# connector-bottom-j2-1.net
KiCad netlist of a schematic drawn in Altium Designer
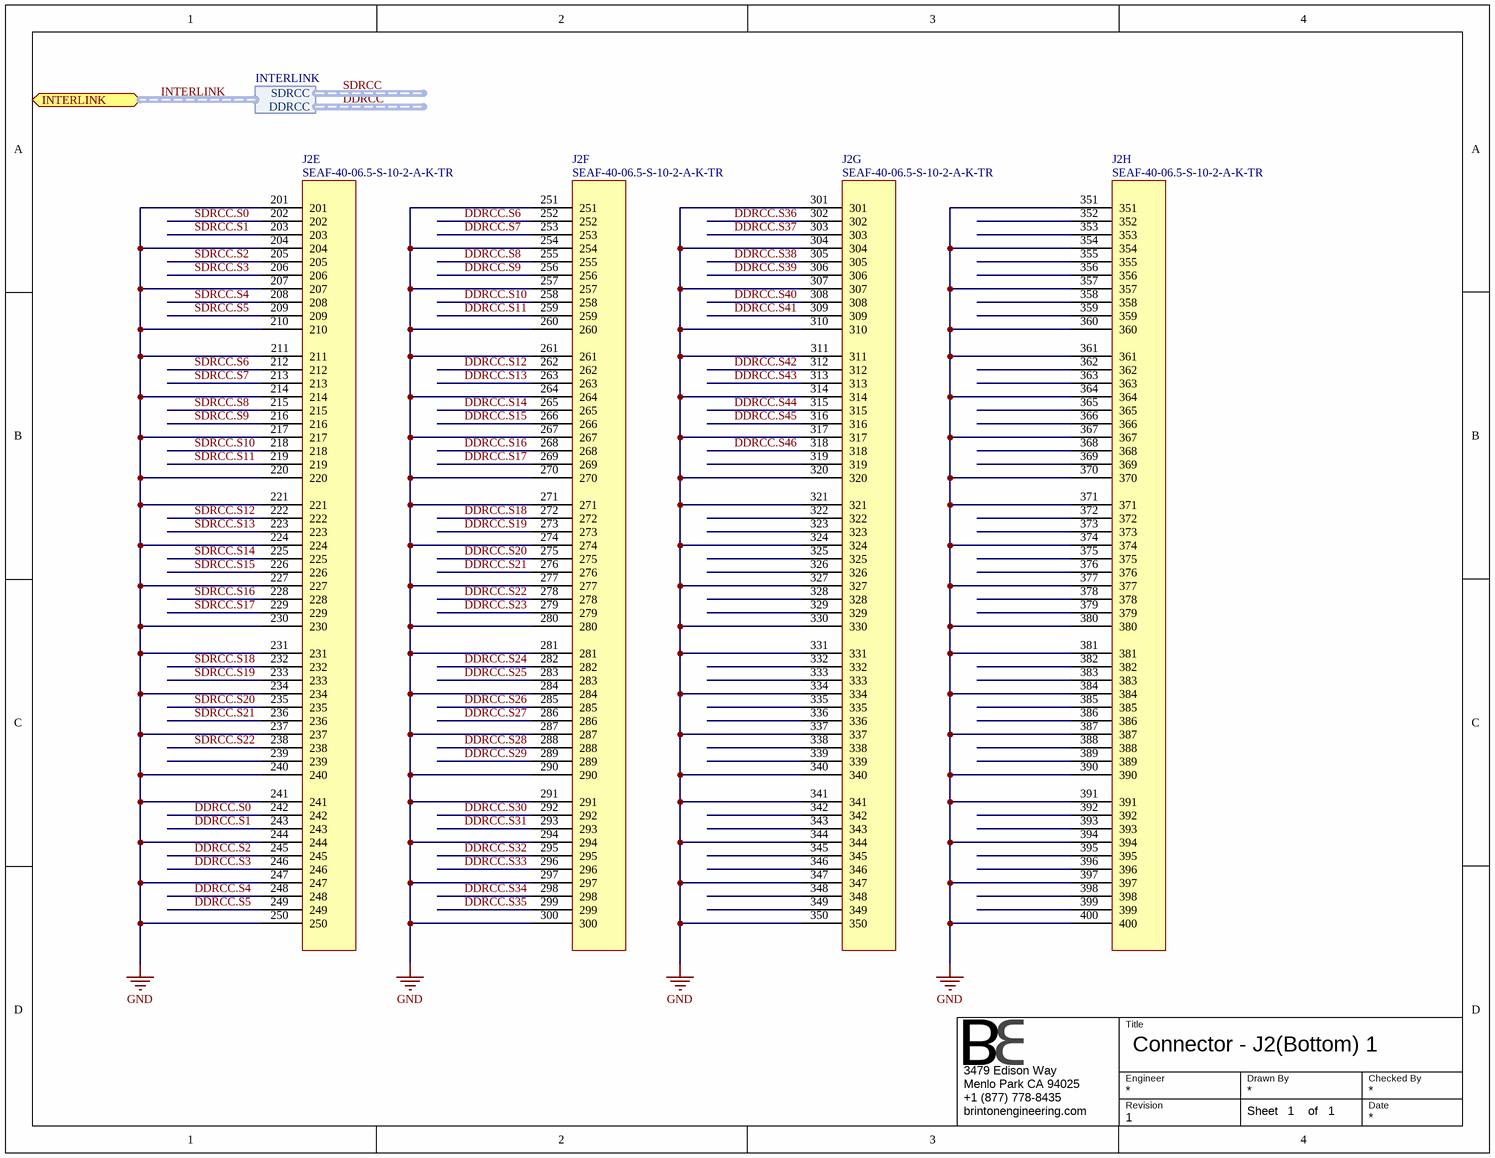
[diagram p0: connector-bottom-j2-1.SchDoc]

(export (version "E")
  (design (tool "Eeschema 10.0.6"))
  (components
    (comp (ref "J2")
      (value "SEAF-40-06.5-S-10-2-A-K-TR")
      (footprint "samtec:SEAF-40-06.5-S-10-2-A-K-TR")
      (description "Terminal Array Assembly, Surface Mount, 0.050\" Pitch, 400 Pins")
      (fields (field (name "MANUFACTURER") "Samtec"))
      (libsource (lib "samtec") (part "SEAF-40-06.5-S-10-2-A-K-TR"))
    )
  )
  (nets
    (net (code "3") (name "/DDRCC.S0") (class "Default")
      (node (ref "J2") (pin "242") (pinfunction "242_242") (pintype "passive"))
    )
    (net (code "4") (name "/DDRCC.S1") (class "Default")
      (node (ref "J2") (pin "243") (pinfunction "243_243") (pintype "passive"))
    )
    (net (code "5") (name "/DDRCC.S2") (class "Default")
      (node (ref "J2") (pin "245") (pinfunction "245_245") (pintype "passive"))
    )
    (net (code "6") (name "/DDRCC.S3") (class "Default")
      (node (ref "J2") (pin "246") (pinfunction "246_246") (pintype "passive"))
    )
    (net (code "7") (name "/DDRCC.S4") (class "Default")
      (node (ref "J2") (pin "248") (pinfunction "248_248") (pintype "passive"))
    )
    (net (code "8") (name "/DDRCC.S5") (class "Default")
      (node (ref "J2") (pin "249") (pinfunction "249_249") (pintype "passive"))
    )
    (net (code "9") (name "/DDRCC.S6") (class "Default")
      (node (ref "J2") (pin "252") (pinfunction "252_252") (pintype "passive"))
    )
    (net (code "10") (name "/DDRCC.S7") (class "Default")
      (node (ref "J2") (pin "253") (pinfunction "253_253") (pintype "passive"))
    )
    (net (code "11") (name "/DDRCC.S8") (class "Default")
      (node (ref "J2") (pin "255") (pinfunction "255_255") (pintype "passive"))
    )
    (net (code "12") (name "/DDRCC.S9") (class "Default")
      (node (ref "J2") (pin "256") (pinfunction "256_256") (pintype "passive"))
    )
    (net (code "13") (name "/DDRCC.S10") (class "Default")
      (node (ref "J2") (pin "258") (pinfunction "258_258") (pintype "passive"))
    )
    (net (code "14") (name "/DDRCC.S11") (class "Default")
      (node (ref "J2") (pin "259") (pinfunction "259_259") (pintype "passive"))
    )
    (net (code "15") (name "/DDRCC.S12") (class "Default")
      (node (ref "J2") (pin "262") (pinfunction "262_262") (pintype "passive"))
    )
    (net (code "16") (name "/DDRCC.S13") (class "Default")
      (node (ref "J2") (pin "263") (pinfunction "263_263") (pintype "passive"))
    )
    (net (code "17") (name "/DDRCC.S14") (class "Default")
      (node (ref "J2") (pin "265") (pinfunction "265_265") (pintype "passive"))
    )
    (net (code "18") (name "/DDRCC.S15") (class "Default")
      (node (ref "J2") (pin "266") (pinfunction "266_266") (pintype "passive"))
    )
    (net (code "19") (name "/DDRCC.S16") (class "Default")
      (node (ref "J2") (pin "268") (pinfunction "268_268") (pintype "passive"))
    )
    (net (code "20") (name "/DDRCC.S17") (class "Default")
      (node (ref "J2") (pin "269") (pinfunction "269_269") (pintype "passive"))
    )
    (net (code "21") (name "/DDRCC.S18") (class "Default")
      (node (ref "J2") (pin "272") (pinfunction "272_272") (pintype "passive"))
    )
    (net (code "22") (name "/DDRCC.S19") (class "Default")
      (node (ref "J2") (pin "273") (pinfunction "273_273") (pintype "passive"))
    )
    (net (code "23") (name "/DDRCC.S20") (class "Default")
      (node (ref "J2") (pin "275") (pinfunction "275_275") (pintype "passive"))
    )
    (net (code "24") (name "/DDRCC.S21") (class "Default")
      (node (ref "J2") (pin "276") (pinfunction "276_276") (pintype "passive"))
    )
    (net (code "25") (name "/DDRCC.S22") (class "Default")
      (node (ref "J2") (pin "278") (pinfunction "278_278") (pintype "passive"))
    )
    (net (code "26") (name "/DDRCC.S23") (class "Default")
      (node (ref "J2") (pin "279") (pinfunction "279_279") (pintype "passive"))
    )
    (net (code "27") (name "/DDRCC.S24") (class "Default")
      (node (ref "J2") (pin "282") (pinfunction "282_282") (pintype "passive"))
    )
    (net (code "28") (name "/DDRCC.S25") (class "Default")
      (node (ref "J2") (pin "283") (pinfunction "283_283") (pintype "passive"))
    )
    (net (code "29") (name "/DDRCC.S26") (class "Default")
      (node (ref "J2") (pin "285") (pinfunction "285_285") (pintype "passive"))
    )
    (net (code "30") (name "/DDRCC.S27") (class "Default")
      (node (ref "J2") (pin "286") (pinfunction "286_286") (pintype "passive"))
    )
    (net (code "31") (name "/DDRCC.S28") (class "Default")
      (node (ref "J2") (pin "288") (pinfunction "288_288") (pintype "passive"))
    )
    (net (code "32") (name "/DDRCC.S29") (class "Default")
      (node (ref "J2") (pin "289") (pinfunction "289_289") (pintype "passive"))
    )
    (net (code "33") (name "/DDRCC.S30") (class "Default")
      (node (ref "J2") (pin "292") (pinfunction "292_292") (pintype "passive"))
    )
    (net (code "34") (name "/DDRCC.S31") (class "Default")
      (node (ref "J2") (pin "293") (pinfunction "293_293") (pintype "passive"))
    )
    (net (code "35") (name "/DDRCC.S32") (class "Default")
      (node (ref "J2") (pin "295") (pinfunction "295_295") (pintype "passive"))
    )
    (net (code "36") (name "/DDRCC.S33") (class "Default")
      (node (ref "J2") (pin "296") (pinfunction "296_296") (pintype "passive"))
    )
    (net (code "37") (name "/DDRCC.S34") (class "Default")
      (node (ref "J2") (pin "298") (pinfunction "298_298") (pintype "passive"))
    )
    (net (code "38") (name "/DDRCC.S35") (class "Default")
      (node (ref "J2") (pin "299") (pinfunction "299_299") (pintype "passive"))
    )
    (net (code "39") (name "/DDRCC.S36") (class "Default")
      (node (ref "J2") (pin "302") (pinfunction "302_302") (pintype "passive"))
    )
    (net (code "40") (name "/DDRCC.S37") (class "Default")
      (node (ref "J2") (pin "303") (pinfunction "303_303") (pintype "passive"))
    )
    (net (code "41") (name "/DDRCC.S38") (class "Default")
      (node (ref "J2") (pin "305") (pinfunction "305_305") (pintype "passive"))
    )
    (net (code "42") (name "/DDRCC.S39") (class "Default")
      (node (ref "J2") (pin "306") (pinfunction "306_306") (pintype "passive"))
    )
    (net (code "43") (name "/DDRCC.S40") (class "Default")
      (node (ref "J2") (pin "308") (pinfunction "308_308") (pintype "passive"))
    )
    (net (code "44") (name "/DDRCC.S41") (class "Default")
      (node (ref "J2") (pin "309") (pinfunction "309_309") (pintype "passive"))
    )
    (net (code "45") (name "/DDRCC.S42") (class "Default")
      (node (ref "J2") (pin "312") (pinfunction "312_312") (pintype "passive"))
    )
    (net (code "46") (name "/DDRCC.S43") (class "Default")
      (node (ref "J2") (pin "313") (pinfunction "313_313") (pintype "passive"))
    )
    (net (code "47") (name "/DDRCC.S44") (class "Default")
      (node (ref "J2") (pin "315") (pinfunction "315_315") (pintype "passive"))
    )
    (net (code "48") (name "/DDRCC.S45") (class "Default")
      (node (ref "J2") (pin "316") (pinfunction "316_316") (pintype "passive"))
    )
    (net (code "49") (name "/DDRCC.S46") (class "Default")
      (node (ref "J2") (pin "318") (pinfunction "318_318") (pintype "passive"))
    )
    (net (code "51") (name "/SDRCC.S0") (class "Default")
      (node (ref "J2") (pin "202") (pinfunction "202_202") (pintype "passive"))
    )
    (net (code "52") (name "/SDRCC.S1") (class "Default")
      (node (ref "J2") (pin "203") (pinfunction "203_203") (pintype "passive"))
    )
    (net (code "53") (name "/SDRCC.S2") (class "Default")
      (node (ref "J2") (pin "205") (pinfunction "205_205") (pintype "passive"))
    )
    (net (code "54") (name "/SDRCC.S3") (class "Default")
      (node (ref "J2") (pin "206") (pinfunction "206_206") (pintype "passive"))
    )
    (net (code "55") (name "/SDRCC.S4") (class "Default")
      (node (ref "J2") (pin "208") (pinfunction "208_208") (pintype "passive"))
    )
    (net (code "56") (name "/SDRCC.S5") (class "Default")
      (node (ref "J2") (pin "209") (pinfunction "209_209") (pintype "passive"))
    )
    (net (code "57") (name "/SDRCC.S6") (class "Default")
      (node (ref "J2") (pin "212") (pinfunction "212_212") (pintype "passive"))
    )
    (net (code "58") (name "/SDRCC.S7") (class "Default")
      (node (ref "J2") (pin "213") (pinfunction "213_213") (pintype "passive"))
    )
    (net (code "59") (name "/SDRCC.S8") (class "Default")
      (node (ref "J2") (pin "215") (pinfunction "215_215") (pintype "passive"))
    )
    (net (code "60") (name "/SDRCC.S9") (class "Default")
      (node (ref "J2") (pin "216") (pinfunction "216_216") (pintype "passive"))
    )
    (net (code "61") (name "/SDRCC.S10") (class "Default")
      (node (ref "J2") (pin "218") (pinfunction "218_218") (pintype "passive"))
    )
    (net (code "62") (name "/SDRCC.S11") (class "Default")
      (node (ref "J2") (pin "219") (pinfunction "219_219") (pintype "passive"))
    )
    (net (code "63") (name "/SDRCC.S12") (class "Default")
      (node (ref "J2") (pin "222") (pinfunction "222_222") (pintype "passive"))
    )
    (net (code "64") (name "/SDRCC.S13") (class "Default")
      (node (ref "J2") (pin "223") (pinfunction "223_223") (pintype "passive"))
    )
    (net (code "65") (name "/SDRCC.S14") (class "Default")
      (node (ref "J2") (pin "225") (pinfunction "225_225") (pintype "passive"))
    )
    (net (code "66") (name "/SDRCC.S15") (class "Default")
      (node (ref "J2") (pin "226") (pinfunction "226_226") (pintype "passive"))
    )
    (net (code "67") (name "/SDRCC.S16") (class "Default")
      (node (ref "J2") (pin "228") (pinfunction "228_228") (pintype "passive"))
    )
    (net (code "68") (name "/SDRCC.S17") (class "Default")
      (node (ref "J2") (pin "229") (pinfunction "229_229") (pintype "passive"))
    )
    (net (code "69") (name "/SDRCC.S18") (class "Default")
      (node (ref "J2") (pin "232") (pinfunction "232_232") (pintype "passive"))
    )
    (net (code "70") (name "/SDRCC.S19") (class "Default")
      (node (ref "J2") (pin "233") (pinfunction "233_233") (pintype "passive"))
    )
    (net (code "71") (name "/SDRCC.S20") (class "Default")
      (node (ref "J2") (pin "235") (pinfunction "235_235") (pintype "passive"))
    )
    (net (code "72") (name "/SDRCC.S21") (class "Default")
      (node (ref "J2") (pin "236") (pinfunction "236_236") (pintype "passive"))
    )
    (net (code "73") (name "/SDRCC.S22") (class "Default")
      (node (ref "J2") (pin "238") (pinfunction "238_238") (pintype "passive"))
    )
    (net (code "75") (name "GND") (class "Default")
      (node (ref "J2") (pin "201") (pinfunction "201_201") (pintype "passive"))
      (node (ref "J2") (pin "204") (pinfunction "204_204") (pintype "passive"))
      (node (ref "J2") (pin "207") (pinfunction "207_207") (pintype "passive"))
      (node (ref "J2") (pin "210") (pinfunction "210_210") (pintype "passive"))
      (node (ref "J2") (pin "211") (pinfunction "211_211") (pintype "passive"))
      (node (ref "J2") (pin "214") (pinfunction "214_214") (pintype "passive"))
      (node (ref "J2") (pin "217") (pinfunction "217_217") (pintype "passive"))
      (node (ref "J2") (pin "220") (pinfunction "220_220") (pintype "passive"))
      (node (ref "J2") (pin "221") (pinfunction "221_221") (pintype "passive"))
      (node (ref "J2") (pin "224") (pinfunction "224_224") (pintype "passive"))
      (node (ref "J2") (pin "227") (pinfunction "227_227") (pintype "passive"))
      (node (ref "J2") (pin "230") (pinfunction "230_230") (pintype "passive"))
      (node (ref "J2") (pin "231") (pinfunction "231_231") (pintype "passive"))
      (node (ref "J2") (pin "234") (pinfunction "234_234") (pintype "passive"))
      (node (ref "J2") (pin "237") (pinfunction "237_237") (pintype "passive"))
      (node (ref "J2") (pin "240") (pinfunction "240_240") (pintype "passive"))
      (node (ref "J2") (pin "241") (pinfunction "241_241") (pintype "passive"))
      (node (ref "J2") (pin "244") (pinfunction "244_244") (pintype "passive"))
      (node (ref "J2") (pin "247") (pinfunction "247_247") (pintype "passive"))
      (node (ref "J2") (pin "250") (pinfunction "250_250") (pintype "passive"))
      (node (ref "J2") (pin "251") (pinfunction "251_251") (pintype "passive"))
      (node (ref "J2") (pin "254") (pinfunction "254_254") (pintype "passive"))
      (node (ref "J2") (pin "257") (pinfunction "257_257") (pintype "passive"))
      (node (ref "J2") (pin "260") (pinfunction "260_260") (pintype "passive"))
      (node (ref "J2") (pin "261") (pinfunction "261_261") (pintype "passive"))
      (node (ref "J2") (pin "264") (pinfunction "264_264") (pintype "passive"))
      (node (ref "J2") (pin "267") (pinfunction "267_267") (pintype "passive"))
      (node (ref "J2") (pin "270") (pinfunction "270_270") (pintype "passive"))
      (node (ref "J2") (pin "271") (pinfunction "271_271") (pintype "passive"))
      (node (ref "J2") (pin "274") (pinfunction "274_274") (pintype "passive"))
      (node (ref "J2") (pin "277") (pinfunction "277_277") (pintype "passive"))
      (node (ref "J2") (pin "280") (pinfunction "280_280") (pintype "passive"))
      (node (ref "J2") (pin "281") (pinfunction "281_281") (pintype "passive"))
      (node (ref "J2") (pin "284") (pinfunction "284_284") (pintype "passive"))
      (node (ref "J2") (pin "287") (pinfunction "287_287") (pintype "passive"))
      (node (ref "J2") (pin "290") (pinfunction "290_290") (pintype "passive"))
      (node (ref "J2") (pin "291") (pinfunction "291_291") (pintype "passive"))
      (node (ref "J2") (pin "294") (pinfunction "294_294") (pintype "passive"))
      (node (ref "J2") (pin "297") (pinfunction "297_297") (pintype "passive"))
      (node (ref "J2") (pin "300") (pinfunction "300_300") (pintype "passive"))
      (node (ref "J2") (pin "301") (pinfunction "301_301") (pintype "passive"))
      (node (ref "J2") (pin "304") (pinfunction "304_304") (pintype "passive"))
      (node (ref "J2") (pin "307") (pinfunction "307_307") (pintype "passive"))
      (node (ref "J2") (pin "310") (pinfunction "310_310") (pintype "passive"))
      (node (ref "J2") (pin "311") (pinfunction "311_311") (pintype "passive"))
      (node (ref "J2") (pin "314") (pinfunction "314_314") (pintype "passive"))
      (node (ref "J2") (pin "317") (pinfunction "317_317") (pintype "passive"))
      (node (ref "J2") (pin "320") (pinfunction "320_320") (pintype "passive"))
      (node (ref "J2") (pin "321") (pinfunction "321_321") (pintype "passive"))
      (node (ref "J2") (pin "324") (pinfunction "324_324") (pintype "passive"))
      (node (ref "J2") (pin "327") (pinfunction "327_327") (pintype "passive"))
      (node (ref "J2") (pin "330") (pinfunction "330_330") (pintype "passive"))
      (node (ref "J2") (pin "331") (pinfunction "331_331") (pintype "passive"))
      (node (ref "J2") (pin "334") (pinfunction "334_334") (pintype "passive"))
      (node (ref "J2") (pin "337") (pinfunction "337_337") (pintype "passive"))
      (node (ref "J2") (pin "340") (pinfunction "340_340") (pintype "passive"))
      (node (ref "J2") (pin "341") (pinfunction "341_341") (pintype "passive"))
      (node (ref "J2") (pin "344") (pinfunction "344_344") (pintype "passive"))
      (node (ref "J2") (pin "347") (pinfunction "347_347") (pintype "passive"))
      (node (ref "J2") (pin "350") (pinfunction "350_350") (pintype "passive"))
      (node (ref "J2") (pin "351") (pinfunction "351_351") (pintype "passive"))
      (node (ref "J2") (pin "354") (pinfunction "354_354") (pintype "passive"))
      (node (ref "J2") (pin "357") (pinfunction "357_357") (pintype "passive"))
      (node (ref "J2") (pin "360") (pinfunction "360_360") (pintype "passive"))
      (node (ref "J2") (pin "361") (pinfunction "361_361") (pintype "passive"))
      (node (ref "J2") (pin "364") (pinfunction "364_364") (pintype "passive"))
      (node (ref "J2") (pin "367") (pinfunction "367_367") (pintype "passive"))
      (node (ref "J2") (pin "370") (pinfunction "370_370") (pintype "passive"))
      (node (ref "J2") (pin "371") (pinfunction "371_371") (pintype "passive"))
      (node (ref "J2") (pin "374") (pinfunction "374_374") (pintype "passive"))
      (node (ref "J2") (pin "377") (pinfunction "377_377") (pintype "passive"))
      (node (ref "J2") (pin "380") (pinfunction "380_380") (pintype "passive"))
      (node (ref "J2") (pin "381") (pinfunction "381_381") (pintype "passive"))
      (node (ref "J2") (pin "384") (pinfunction "384_384") (pintype "passive"))
      (node (ref "J2") (pin "387") (pinfunction "387_387") (pintype "passive"))
      (node (ref "J2") (pin "390") (pinfunction "390_390") (pintype "passive"))
      (node (ref "J2") (pin "391") (pinfunction "391_391") (pintype "passive"))
      (node (ref "J2") (pin "394") (pinfunction "394_394") (pintype "passive"))
      (node (ref "J2") (pin "397") (pinfunction "397_397") (pintype "passive"))
      (node (ref "J2") (pin "400") (pinfunction "400_400") (pintype "passive"))
    )
    (net (code "76") (name "unconnected-(J2-Pad239)") (class "Default")
      (node (ref "J2") (pin "239") (pinfunction "239_239") (pintype "passive"))
    )
    (net (code "77") (name "unconnected-(J2-Pad319)") (class "Default")
      (node (ref "J2") (pin "319") (pinfunction "319_319") (pintype "passive"))
    )
    (net (code "78") (name "unconnected-(J2-Pad322)") (class "Default")
      (node (ref "J2") (pin "322") (pinfunction "322_322") (pintype "passive"))
    )
    (net (code "79") (name "unconnected-(J2-Pad323)") (class "Default")
      (node (ref "J2") (pin "323") (pinfunction "323_323") (pintype "passive"))
    )
    (net (code "80") (name "unconnected-(J2-Pad325)") (class "Default")
      (node (ref "J2") (pin "325") (pinfunction "325_325") (pintype "passive"))
    )
    (net (code "81") (name "unconnected-(J2-Pad326)") (class "Default")
      (node (ref "J2") (pin "326") (pinfunction "326_326") (pintype "passive"))
    )
    (net (code "82") (name "unconnected-(J2-Pad328)") (class "Default")
      (node (ref "J2") (pin "328") (pinfunction "328_328") (pintype "passive"))
    )
    (net (code "83") (name "unconnected-(J2-Pad329)") (class "Default")
      (node (ref "J2") (pin "329") (pinfunction "329_329") (pintype "passive"))
    )
    (net (code "84") (name "unconnected-(J2-Pad332)") (class "Default")
      (node (ref "J2") (pin "332") (pinfunction "332_332") (pintype "passive"))
    )
    (net (code "85") (name "unconnected-(J2-Pad333)") (class "Default")
      (node (ref "J2") (pin "333") (pinfunction "333_333") (pintype "passive"))
    )
    (net (code "86") (name "unconnected-(J2-Pad335)") (class "Default")
      (node (ref "J2") (pin "335") (pinfunction "335_335") (pintype "passive"))
    )
    (net (code "87") (name "unconnected-(J2-Pad336)") (class "Default")
      (node (ref "J2") (pin "336") (pinfunction "336_336") (pintype "passive"))
    )
    (net (code "88") (name "unconnected-(J2-Pad338)") (class "Default")
      (node (ref "J2") (pin "338") (pinfunction "338_338") (pintype "passive"))
    )
    (net (code "89") (name "unconnected-(J2-Pad339)") (class "Default")
      (node (ref "J2") (pin "339") (pinfunction "339_339") (pintype "passive"))
    )
    (net (code "90") (name "unconnected-(J2-Pad342)") (class "Default")
      (node (ref "J2") (pin "342") (pinfunction "342_342") (pintype "passive"))
    )
    (net (code "91") (name "unconnected-(J2-Pad343)") (class "Default")
      (node (ref "J2") (pin "343") (pinfunction "343_343") (pintype "passive"))
    )
    (net (code "92") (name "unconnected-(J2-Pad345)") (class "Default")
      (node (ref "J2") (pin "345") (pinfunction "345_345") (pintype "passive"))
    )
    (net (code "93") (name "unconnected-(J2-Pad346)") (class "Default")
      (node (ref "J2") (pin "346") (pinfunction "346_346") (pintype "passive"))
    )
    (net (code "94") (name "unconnected-(J2-Pad348)") (class "Default")
      (node (ref "J2") (pin "348") (pinfunction "348_348") (pintype "passive"))
    )
    (net (code "95") (name "unconnected-(J2-Pad349)") (class "Default")
      (node (ref "J2") (pin "349") (pinfunction "349_349") (pintype "passive"))
    )
    (net (code "96") (name "unconnected-(J2-Pad352)") (class "Default")
      (node (ref "J2") (pin "352") (pinfunction "352_352") (pintype "passive"))
    )
    (net (code "97") (name "unconnected-(J2-Pad353)") (class "Default")
      (node (ref "J2") (pin "353") (pinfunction "353_353") (pintype "passive"))
    )
    (net (code "98") (name "unconnected-(J2-Pad355)") (class "Default")
      (node (ref "J2") (pin "355") (pinfunction "355_355") (pintype "passive"))
    )
    (net (code "99") (name "unconnected-(J2-Pad356)") (class "Default")
      (node (ref "J2") (pin "356") (pinfunction "356_356") (pintype "passive"))
    )
    (net (code "100") (name "unconnected-(J2-Pad358)") (class "Default")
      (node (ref "J2") (pin "358") (pinfunction "358_358") (pintype "passive"))
    )
    (net (code "101") (name "unconnected-(J2-Pad359)") (class "Default")
      (node (ref "J2") (pin "359") (pinfunction "359_359") (pintype "passive"))
    )
    (net (code "102") (name "unconnected-(J2-Pad362)") (class "Default")
      (node (ref "J2") (pin "362") (pinfunction "362_362") (pintype "passive"))
    )
    (net (code "103") (name "unconnected-(J2-Pad363)") (class "Default")
      (node (ref "J2") (pin "363") (pinfunction "363_363") (pintype "passive"))
    )
    (net (code "104") (name "unconnected-(J2-Pad365)") (class "Default")
      (node (ref "J2") (pin "365") (pinfunction "365_365") (pintype "passive"))
    )
    (net (code "105") (name "unconnected-(J2-Pad366)") (class "Default")
      (node (ref "J2") (pin "366") (pinfunction "366_366") (pintype "passive"))
    )
    (net (code "106") (name "unconnected-(J2-Pad368)") (class "Default")
      (node (ref "J2") (pin "368") (pinfunction "368_368") (pintype "passive"))
    )
    (net (code "107") (name "unconnected-(J2-Pad369)") (class "Default")
      (node (ref "J2") (pin "369") (pinfunction "369_369") (pintype "passive"))
    )
    (net (code "108") (name "unconnected-(J2-Pad372)") (class "Default")
      (node (ref "J2") (pin "372") (pinfunction "372_372") (pintype "passive"))
    )
    (net (code "109") (name "unconnected-(J2-Pad373)") (class "Default")
      (node (ref "J2") (pin "373") (pinfunction "373_373") (pintype "passive"))
    )
    (net (code "110") (name "unconnected-(J2-Pad375)") (class "Default")
      (node (ref "J2") (pin "375") (pinfunction "375_375") (pintype "passive"))
    )
    (net (code "111") (name "unconnected-(J2-Pad376)") (class "Default")
      (node (ref "J2") (pin "376") (pinfunction "376_376") (pintype "passive"))
    )
    (net (code "112") (name "unconnected-(J2-Pad378)") (class "Default")
      (node (ref "J2") (pin "378") (pinfunction "378_378") (pintype "passive"))
    )
    (net (code "113") (name "unconnected-(J2-Pad379)") (class "Default")
      (node (ref "J2") (pin "379") (pinfunction "379_379") (pintype "passive"))
    )
    (net (code "114") (name "unconnected-(J2-Pad382)") (class "Default")
      (node (ref "J2") (pin "382") (pinfunction "382_382") (pintype "passive"))
    )
    (net (code "115") (name "unconnected-(J2-Pad383)") (class "Default")
      (node (ref "J2") (pin "383") (pinfunction "383_383") (pintype "passive"))
    )
    (net (code "116") (name "unconnected-(J2-Pad385)") (class "Default")
      (node (ref "J2") (pin "385") (pinfunction "385_385") (pintype "passive"))
    )
    (net (code "117") (name "unconnected-(J2-Pad386)") (class "Default")
      (node (ref "J2") (pin "386") (pinfunction "386_386") (pintype "passive"))
    )
    (net (code "118") (name "unconnected-(J2-Pad388)") (class "Default")
      (node (ref "J2") (pin "388") (pinfunction "388_388") (pintype "passive"))
    )
    (net (code "119") (name "unconnected-(J2-Pad389)") (class "Default")
      (node (ref "J2") (pin "389") (pinfunction "389_389") (pintype "passive"))
    )
    (net (code "120") (name "unconnected-(J2-Pad392)") (class "Default")
      (node (ref "J2") (pin "392") (pinfunction "392_392") (pintype "passive"))
    )
    (net (code "121") (name "unconnected-(J2-Pad393)") (class "Default")
      (node (ref "J2") (pin "393") (pinfunction "393_393") (pintype "passive"))
    )
    (net (code "122") (name "unconnected-(J2-Pad395)") (class "Default")
      (node (ref "J2") (pin "395") (pinfunction "395_395") (pintype "passive"))
    )
    (net (code "123") (name "unconnected-(J2-Pad396)") (class "Default")
      (node (ref "J2") (pin "396") (pinfunction "396_396") (pintype "passive"))
    )
    (net (code "124") (name "unconnected-(J2-Pad398)") (class "Default")
      (node (ref "J2") (pin "398") (pinfunction "398_398") (pintype "passive"))
    )
    (net (code "125") (name "unconnected-(J2-Pad399)") (class "Default")
      (node (ref "J2") (pin "399") (pinfunction "399_399") (pintype "passive"))
    )
  )
)
